# STM32F103_sensor_v0_0.net
KiCad netlist of a schematic drawn in Altium Designer
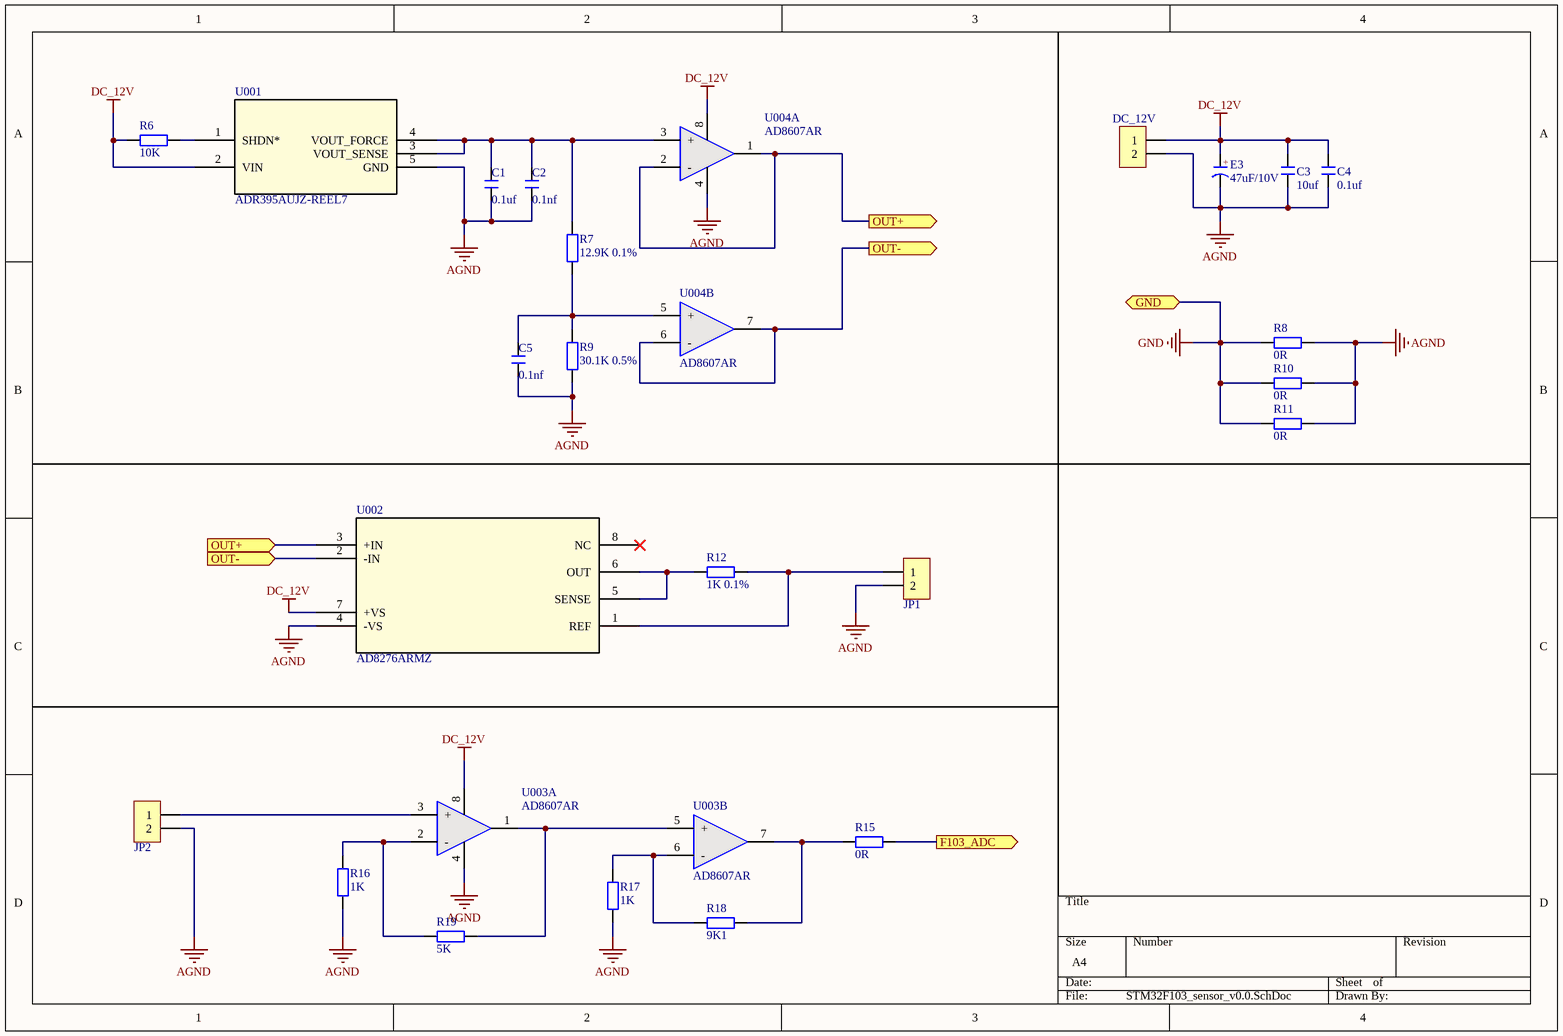
[diagram p0: STM32F103_sensor_v0.0.SchDoc]

(export (version "E")
  (design (tool "Eeschema 10.0.6"))
  (components
    (comp (ref "C1")
      (value "0.1uf")
      (footprint "C 0603")
      (description "无极性贴片电容")
      (fields (field (name "版权归属") "源创客"))
      (libsource (lib "电阻-电容-电感") (part "C"))
    )
    (comp (ref "C2")
      (value "0.1nf")
      (footprint "C 0603")
      (description "无极性贴片电容")
      (fields (field (name "版权归属") "源创客"))
      (libsource (lib "电阻-电容-电感") (part "C"))
    )
    (comp (ref "C3")
      (value "10uf")
      (footprint "C 0603")
      (description "无极性贴片电容")
      (fields (field (name "版权归属") "源创客"))
      (libsource (lib "电阻-电容-电感") (part "C"))
    )
    (comp (ref "C4")
      (value "0.1uf")
      (footprint "C 0603")
      (description "无极性贴片电容")
      (fields (field (name "版权归属") "源创客"))
      (libsource (lib "电阻-电容-电感") (part "C"))
    )
    (comp (ref "C5")
      (value "0.1nf")
      (footprint "C 0603")
      (description "无极性贴片电容")
      (fields (field (name "版权归属") "源创客"))
      (libsource (lib "电阻-电容-电感") (part "C"))
    )
    (comp (ref "DC_12V")
      (value "HDR-1X2")
      (footprint "HDR-1X2")
      (description "2P接插件")
      (fields (field (name "版权归属") "源创客"))
      (libsource (lib "接插件") (part "Header 2"))
    )
    (comp (ref "E3")
      (value "47uF/10V")
      (footprint "CT 5*6 - C")
      (description "贴片固态电容")
      (fields (field (name "版权归属") "源创客"))
      (libsource (lib "电阻-电容-电感") (part "C-CT"))
    )
    (comp (ref "JP1")
      (value "HDR-1X2")
      (footprint "HDR-1X2")
      (description "2P接插件")
      (fields (field (name "版权归属") "源创客"))
      (libsource (lib "") (part "Header 2_1"))
    )
    (comp (ref "JP2")
      (value "HDR-1X2")
      (footprint "HDR-1X2")
      (description "2P接插件")
      (fields (field (name "版权归属") "源创客"))
      (libsource (lib "接插件") (part "Header 2"))
    )
    (comp (ref "R6")
      (value "10K")
      (footprint "R 0805")
      (description "贴片电阻")
      (fields (field (name "版权归属") "源创客"))
      (libsource (lib "电阻-电容-电感") (part "R"))
    )
    (comp (ref "R7")
      (value "12.9K 0.1%")
      (footprint "R 0805")
      (description "贴片电阻")
      (fields (field (name "版权归属") "源创客"))
      (libsource (lib "电阻-电容-电感") (part "R"))
    )
    (comp (ref "R8")
      (value "0R")
      (footprint "R 1206")
      (description "贴片电阻")
      (fields (field (name "版权归属") "源创客"))
      (libsource (lib "电阻-电容-电感") (part "R"))
    )
    (comp (ref "R9")
      (value "30.1K 0.5%")
      (footprint "R 0805")
      (description "贴片电阻")
      (fields (field (name "版权归属") "源创客"))
      (libsource (lib "电阻-电容-电感") (part "R"))
    )
    (comp (ref "R10")
      (value "0R")
      (footprint "R 1206")
      (description "贴片电阻")
      (fields (field (name "版权归属") "源创客"))
      (libsource (lib "电阻-电容-电感") (part "R"))
    )
    (comp (ref "R11")
      (value "0R")
      (footprint "R 1206")
      (description "贴片电阻")
      (fields (field (name "版权归属") "源创客"))
      (libsource (lib "电阻-电容-电感") (part "R"))
    )
    (comp (ref "R12")
      (value "1K 0.1%")
      (footprint "R 0805")
      (description "贴片电阻")
      (fields (field (name "版权归属") "源创客"))
      (libsource (lib "电阻-电容-电感") (part "R"))
    )
    (comp (ref "R15")
      (value "0R")
      (footprint "R 0805")
      (description "贴片电阻")
      (fields (field (name "版权归属") "源创客"))
      (libsource (lib "电阻-电容-电感") (part "R"))
    )
    (comp (ref "R16")
      (value "1K")
      (footprint "R 0805")
      (description "贴片电阻")
      (fields (field (name "版权归属") "源创客"))
      (libsource (lib "电阻-电容-电感") (part "R"))
    )
    (comp (ref "R17")
      (value "1K")
      (footprint "R 0805")
      (description "贴片电阻")
      (fields (field (name "版权归属") "源创客"))
      (libsource (lib "电阻-电容-电感") (part "R"))
    )
    (comp (ref "R18")
      (value "9K1")
      (footprint "R 0805")
      (description "贴片电阻")
      (fields (field (name "版权归属") "源创客"))
      (libsource (lib "电阻-电容-电感") (part "R"))
    )
    (comp (ref "R19")
      (value "5K")
      (footprint "R 0805")
      (description "贴片电阻")
      (fields (field (name "版权归属") "源创客"))
      (libsource (lib "电阻-电容-电感") (part "R"))
    )
    (comp (ref "U001")
      (value "ADR395AUJZ-REEL7")
      (footprint "SOT23-5L")
      (libsource (lib "STM32F103") (part "ADR395AUJZ-REEL7"))
    )
    (comp (ref "U002")
      (value "AD8276ARMZ")
      (footprint "RM_8")
      (libsource (lib "STM32F103") (part "AD8276ARMZ"))
    )
    (comp (ref "U003")
      (value "AD8607AR")
      (footprint "SOP8_N")
      (description "双运放")
      (fields (field (name "版权归属") "源创客"))
      (libsource (lib "IC芯片") (part "AD8607AR"))
    )
    (comp (ref "U004")
      (value "AD8607AR")
      (footprint "SOP8_N")
      (description "双运放")
      (fields (field (name "版权归属") "源创客"))
      (libsource (lib "IC芯片") (part "AD8607AR"))
    )
  )
  (nets
    (net (code "1") (name "/F103_ADC") (class "Default")
      (node (ref "R15") (pin "2") (pinfunction "2_2") (pintype "passive"))
    )
    (net (code "2") (name "/OUT+") (class "Default")
      (node (ref "U002") (pin "3") (pinfunction "+IN_3") (pintype "passive"))
      (node (ref "U004") (pin "1") (pinfunction "OUT1_1") (pintype "passive"))
      (node (ref "U004") (pin "2") (pinfunction "-_2") (pintype "passive"))
    )
    (net (code "3") (name "/OUT-") (class "Default")
      (node (ref "U002") (pin "2") (pinfunction "-IN_2") (pintype "passive"))
      (node (ref "U004") (pin "6") (pinfunction "-_6") (pintype "passive"))
      (node (ref "U004") (pin "7") (pinfunction "OUT2_7") (pintype "passive"))
    )
    (net (code "4") (name "AGND") (class "Default")
      (node (ref "C1") (pin "1") (pinfunction "1_1") (pintype "passive"))
      (node (ref "C2") (pin "1") (pinfunction "1_1") (pintype "passive"))
      (node (ref "C3") (pin "1") (pinfunction "1_1") (pintype "passive"))
      (node (ref "C4") (pin "1") (pinfunction "1_1") (pintype "passive"))
      (node (ref "C5") (pin "1") (pinfunction "1_1") (pintype "passive"))
      (node (ref "DC_12V") (pin "2") (pinfunction "2_2") (pintype "passive"))
      (node (ref "E3") (pin "2") (pinfunction "K_2") (pintype "passive"))
      (node (ref "JP1") (pin "2") (pinfunction "2_2") (pintype "passive"))
      (node (ref "JP2") (pin "2") (pinfunction "2_2") (pintype "passive"))
      (node (ref "R10") (pin "2") (pinfunction "2_2") (pintype "passive"))
      (node (ref "R11") (pin "2") (pinfunction "2_2") (pintype "passive"))
      (node (ref "R16") (pin "1") (pinfunction "1_1") (pintype "passive"))
      (node (ref "R17") (pin "1") (pinfunction "1_1") (pintype "passive"))
      (node (ref "R8") (pin "2") (pinfunction "2_2") (pintype "passive"))
      (node (ref "R9") (pin "2") (pinfunction "2_2") (pintype "passive"))
      (node (ref "U001") (pin "5") (pinfunction "GND_5") (pintype "passive"))
      (node (ref "U002") (pin "4") (pinfunction "-VS_4") (pintype "passive"))
      (node (ref "U003") (pin "4") (pinfunction "V-_4") (pintype "power_in"))
      (node (ref "U004") (pin "4") (pinfunction "V-_4") (pintype "power_in"))
    )
    (net (code "5") (name "DC_12V") (class "Default")
      (node (ref "C3") (pin "2") (pinfunction "2_2") (pintype "passive"))
      (node (ref "C4") (pin "2") (pinfunction "2_2") (pintype "passive"))
      (node (ref "DC_12V") (pin "1") (pinfunction "1_1") (pintype "passive"))
      (node (ref "E3") (pin "1") (pinfunction "A_1") (pintype "passive"))
      (node (ref "R6") (pin "2") (pinfunction "2_2") (pintype "passive"))
      (node (ref "U001") (pin "2") (pinfunction "VIN_2") (pintype "passive"))
      (node (ref "U002") (pin "7") (pinfunction "+VS_7") (pintype "passive"))
      (node (ref "U003") (pin "8") (pinfunction "V+_8") (pintype "power_in"))
      (node (ref "U004") (pin "8") (pinfunction "V+_8") (pintype "power_in"))
    )
    (net (code "6") (name "GND") (class "Default")
      (node (ref "R10") (pin "1") (pinfunction "1_1") (pintype "passive"))
      (node (ref "R11") (pin "1") (pinfunction "1_1") (pintype "passive"))
      (node (ref "R8") (pin "1") (pinfunction "1_1") (pintype "passive"))
    )
    (net (code "7") (name "Net-(U001-SHDN*)") (class "Default")
      (node (ref "R6") (pin "1") (pinfunction "1_1") (pintype "passive"))
      (node (ref "U001") (pin "1") (pinfunction "SHDN*_1") (pintype "passive"))
    )
    (net (code "8") (name "Net-(U001-VOUT_FORCE)") (class "Default")
      (node (ref "C1") (pin "2") (pinfunction "2_2") (pintype "passive"))
      (node (ref "C2") (pin "2") (pinfunction "2_2") (pintype "passive"))
      (node (ref "R7") (pin "1") (pinfunction "1_1") (pintype "passive"))
      (node (ref "U001") (pin "3") (pinfunction "VOUT_SENSE_3") (pintype "passive"))
      (node (ref "U001") (pin "4") (pinfunction "VOUT_FORCE_4") (pintype "passive"))
      (node (ref "U004") (pin "3") (pinfunction "+_3") (pintype "passive"))
    )
    (net (code "9") (name "Net-(U002-OUT)") (class "Default")
      (node (ref "R12") (pin "1") (pinfunction "1_1") (pintype "passive"))
      (node (ref "U002") (pin "5") (pinfunction "SENSE_5") (pintype "passive"))
      (node (ref "U002") (pin "6") (pinfunction "OUT_6") (pintype "passive"))
    )
    (net (code "10") (name "Net-(U002-REF)") (class "Default")
      (node (ref "JP1") (pin "1") (pinfunction "1_1") (pintype "passive"))
      (node (ref "R12") (pin "2") (pinfunction "2_2") (pintype "passive"))
      (node (ref "U002") (pin "1") (pinfunction "REF_1") (pintype "passive"))
    )
    (net (code "11") (name "Net-(U003A-+)") (class "Default")
      (node (ref "JP2") (pin "1") (pinfunction "1_1") (pintype "passive"))
      (node (ref "U003") (pin "3") (pinfunction "+_3") (pintype "passive"))
    )
    (net (code "12") (name "Net-(U003A--)") (class "Default")
      (node (ref "R16") (pin "2") (pinfunction "2_2") (pintype "passive"))
      (node (ref "R19") (pin "2") (pinfunction "2_2") (pintype "passive"))
      (node (ref "U003") (pin "2") (pinfunction "-_2") (pintype "passive"))
    )
    (net (code "13") (name "Net-(U003A-OUT1)") (class "Default")
      (node (ref "R19") (pin "1") (pinfunction "1_1") (pintype "passive"))
      (node (ref "U003") (pin "1") (pinfunction "OUT1_1") (pintype "passive"))
      (node (ref "U003") (pin "5") (pinfunction "+_5") (pintype "passive"))
    )
    (net (code "14") (name "Net-(U003B--)") (class "Default")
      (node (ref "R17") (pin "2") (pinfunction "2_2") (pintype "passive"))
      (node (ref "R18") (pin "2") (pinfunction "2_2") (pintype "passive"))
      (node (ref "U003") (pin "6") (pinfunction "-_6") (pintype "passive"))
    )
    (net (code "15") (name "Net-(U003B-OUT2)") (class "Default")
      (node (ref "R15") (pin "1") (pinfunction "1_1") (pintype "passive"))
      (node (ref "R18") (pin "1") (pinfunction "1_1") (pintype "passive"))
      (node (ref "U003") (pin "7") (pinfunction "OUT2_7") (pintype "passive"))
    )
    (net (code "16") (name "Net-(U004B-+)") (class "Default")
      (node (ref "C5") (pin "2") (pinfunction "2_2") (pintype "passive"))
      (node (ref "R7") (pin "2") (pinfunction "2_2") (pintype "passive"))
      (node (ref "R9") (pin "1") (pinfunction "1_1") (pintype "passive"))
      (node (ref "U004") (pin "5") (pinfunction "+_5") (pintype "passive"))
    )
    (net (code "17") (name "unconnected-(U002-NC-Pad8)") (class "Default")
      (node (ref "U002") (pin "8") (pinfunction "NC_8") (pintype "passive+no_connect"))
    )
  )
)
